# sensor.net
KiCad netlist of a schematic drawn in EAGLE
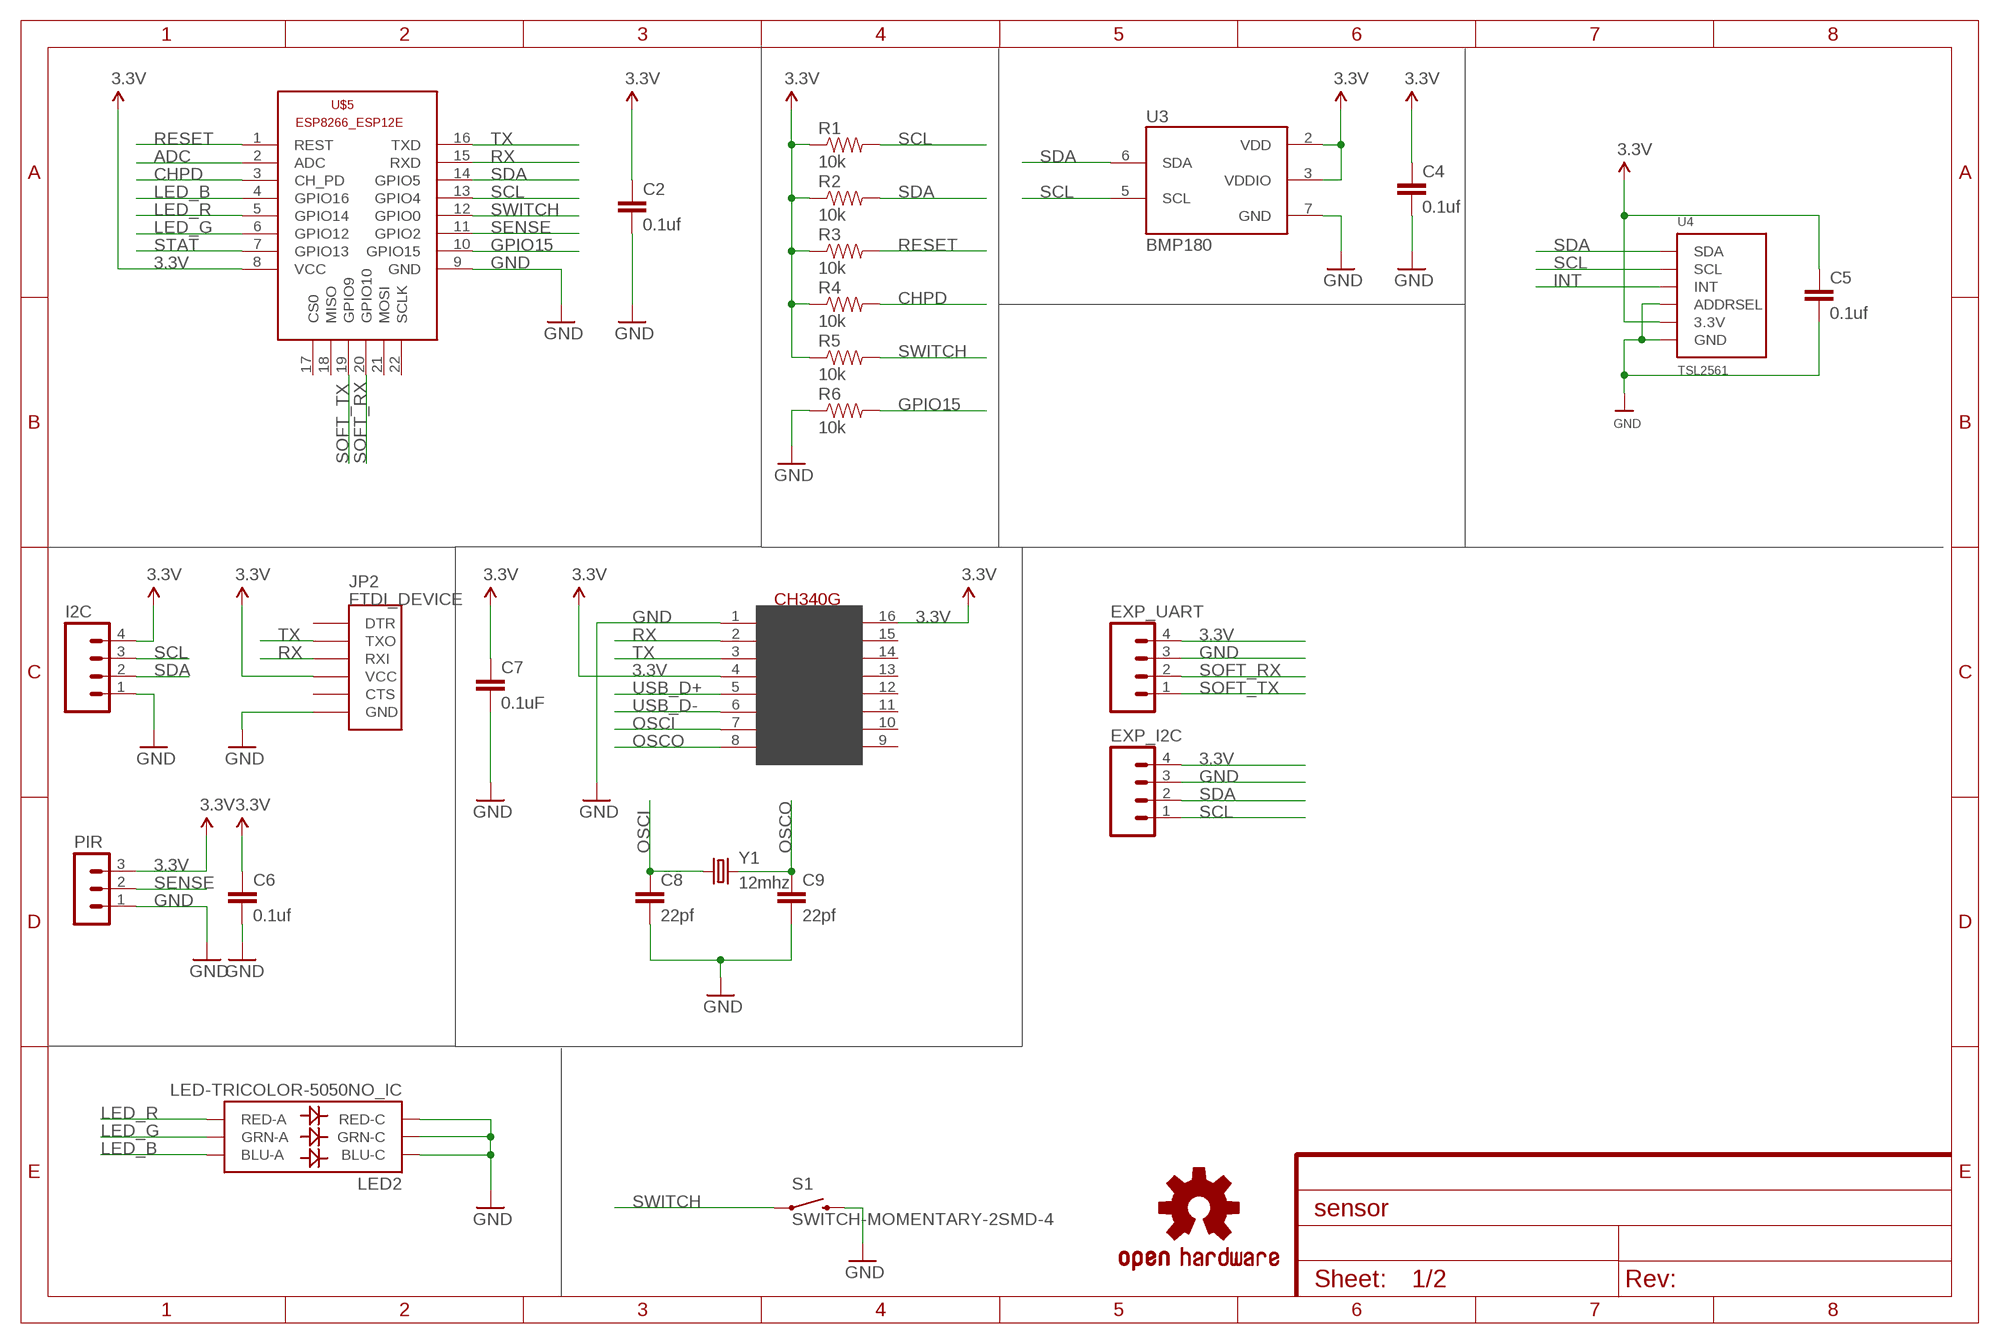
[diagram p0: schematic, sheet 1]
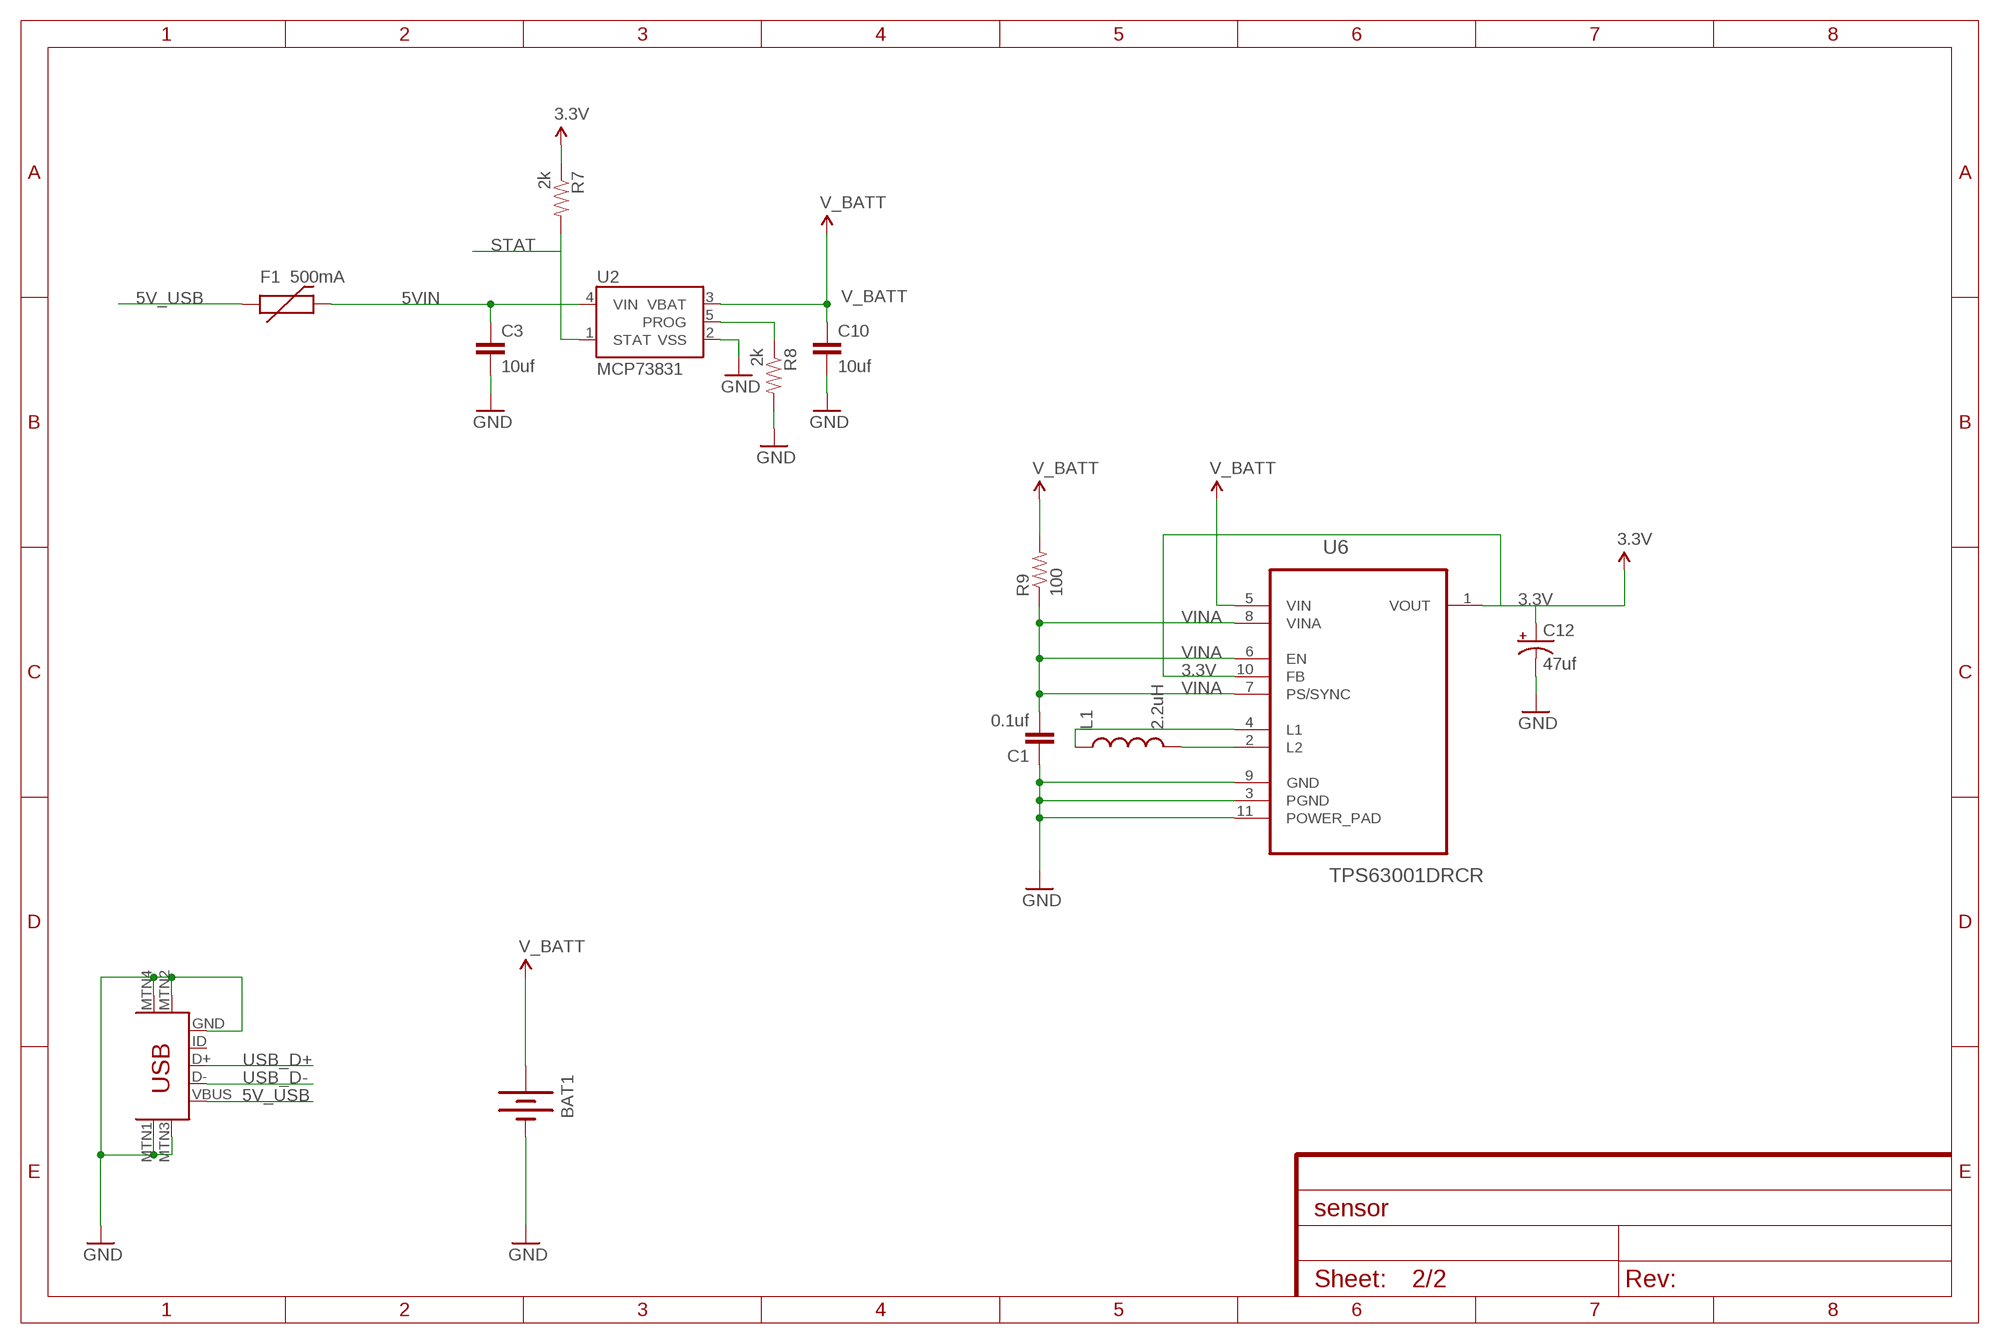
[diagram p1: schematic, sheet 2]

(export (version "E")
  (design (tool "Eeschema 10.0.6"))
  (components
    (comp (ref "BAT1")
      (value "BATTERY18650")
      (footprint "eagle-import:BATTERY_18650-HOLDER")
      (libsource (lib "eagle-import") (part "BATTERY18650"))
    )
    (comp (ref "C1")
      (value "0.1uf")
      (footprint "eagle-import:0805")
      (libsource (lib "eagle-import") (part "CAP0805"))
    )
    (comp (ref "C3")
      (value "10uf")
      (footprint "eagle-import:0805")
      (libsource (lib "eagle-import") (part "CAP0805"))
    )
    (comp (ref "C10")
      (value "10uf")
      (footprint "eagle-import:0805")
      (libsource (lib "eagle-import") (part "CAP0805"))
    )
    (comp (ref "C12")
      (value "47uf")
      (footprint "eagle-import:PANASONIC_C")
      (libsource (lib "eagle-import") (part "CAP_POLC"))
    )
    (comp (ref "F1")
      (value "500mA")
      (footprint "eagle-import:PTC-1206")
      (libsource (lib "eagle-import") (part "PTCSMD"))
    )
    (comp (ref "L1")
      (value "2.2uH")
      (footprint "eagle-import:SRU5028")
      (libsource (lib "eagle-import") (part "INDUCTORSRU5028"))
    )
    (comp (ref "R7")
      (value "2k")
      (footprint "eagle-import:0805")
      (libsource (lib "eagle-import") (part "RESISTOR0805-RES"))
    )
    (comp (ref "R8")
      (value "2k")
      (footprint "eagle-import:0805")
      (libsource (lib "eagle-import") (part "RESISTOR0805-RES"))
    )
    (comp (ref "R9")
      (value "100")
      (footprint "eagle-import:0805")
      (libsource (lib "eagle-import") (part "RESISTOR0805-RES"))
    )
    (comp (ref "U$6")
      (value "USB-MINIB-5PIN")
      (footprint "eagle-import:USB-MINIB")
      (libsource (lib "eagle-import") (part "USB-MINIB-5PIN"))
    )
    (comp (ref "U2")
      (value "MCP73831")
      (footprint "eagle-import:SOT23-5")
      (libsource (lib "eagle-import") (part "MCP73831"))
    )
    (comp (ref "U6")
      (value "TPS63001DRCR")
      (footprint "eagle-import:SON50P300X300X100-11N")
      (libsource (lib "eagle-import") (part "TPS63001DRCR"))
    )
    (comp (ref "C2")
      (value "0.1uf")
      (footprint "eagle-import:0805")
      (libsource (lib "eagle-import") (part "CAP0805"))
    )
    (comp (ref "C4")
      (value "0.1uf")
      (footprint "eagle-import:0805")
      (libsource (lib "eagle-import") (part "CAP0805"))
    )
    (comp (ref "C5")
      (value "0.1uf")
      (footprint "eagle-import:0805")
      (libsource (lib "eagle-import") (part "CAP0805"))
    )
    (comp (ref "C6")
      (value "0.1uf")
      (footprint "eagle-import:0805")
      (libsource (lib "eagle-import") (part "CAP0805"))
    )
    (comp (ref "C7")
      (value "0.1uF")
      (footprint "eagle-import:C0805")
      (libsource (lib "eagle-import") (part "C-EUC0805"))
    )
    (comp (ref "C8")
      (value "22pf")
      (footprint "eagle-import:C0805")
      (libsource (lib "eagle-import") (part "C-EUC0805"))
    )
    (comp (ref "C9")
      (value "22pf")
      (footprint "eagle-import:C0805")
      (libsource (lib "eagle-import") (part "C-EUC0805"))
    )
    (comp (ref "EXP_I2C")
      (value "M04LOCK")
      (footprint "eagle-import:1X04_LOCK")
      (libsource (lib "eagle-import") (part "M04LOCK"))
    )
    (comp (ref "EXP_UART")
      (value "M04LOCK")
      (footprint "eagle-import:1X04_LOCK")
      (libsource (lib "eagle-import") (part "M04LOCK"))
    )
    (comp (ref "I2C")
      (value "M04JST-PTH")
      (footprint "eagle-import:JST-4-PTH")
      (libsource (lib "eagle-import") (part "M04JST-PTH"))
    )
    (comp (ref "JP2")
      (value "FTDI_DEVICE")
      (footprint "eagle-import:FTDI_DEVICE_SIDE")
      (libsource (lib "eagle-import") (part "FTDI_DEVICE"))
    )
    (comp (ref "LED2")
      (value "LED-TRICOLOR-5050NO_IC")
      (footprint "eagle-import:LED-TRICOLOR-5050")
      (libsource (lib "eagle-import") (part "LED-TRICOLOR-5050NO_IC"))
    )
    (comp (ref "LOGO1")
      (value "OSHW-LOGOL")
      (footprint "eagle-import:OSHW-LOGO-L")
      (libsource (lib "eagle-import") (part "OSHW-LOGOL"))
    )
    (comp (ref "PIR")
      (value "MA03-1")
      (footprint "eagle-import:MA03-1")
      (libsource (lib "eagle-import") (part "MA03-1"))
    )
    (comp (ref "R1")
      (value "10k")
      (footprint "eagle-import:0805")
      (libsource (lib "eagle-import") (part "RESISTOR0805-RES"))
    )
    (comp (ref "R2")
      (value "10k")
      (footprint "eagle-import:0805")
      (libsource (lib "eagle-import") (part "RESISTOR0805-RES"))
    )
    (comp (ref "R3")
      (value "10k")
      (footprint "eagle-import:0805")
      (libsource (lib "eagle-import") (part "RESISTOR0805-RES"))
    )
    (comp (ref "R4")
      (value "10k")
      (footprint "eagle-import:0805")
      (libsource (lib "eagle-import") (part "RESISTOR0805-RES"))
    )
    (comp (ref "R5")
      (value "10k")
      (footprint "eagle-import:0805")
      (libsource (lib "eagle-import") (part "RESISTOR0805-RES"))
    )
    (comp (ref "R6")
      (value "10k")
      (footprint "eagle-import:0805")
      (libsource (lib "eagle-import") (part "RESISTOR0805-RES"))
    )
    (comp (ref "S1")
      (value "SWITCH-MOMENTARY-2SMD-4")
      (footprint "eagle-import:TACTILE_SWITCH_TALL")
      (libsource (lib "eagle-import") (part "SWITCH-MOMENTARY-2SMD-4"))
    )
    (comp (ref "U$5")
      (value "ESP8266-12EESP8266-ESP12E")
      (footprint "eagle-import:ESP8266-ESP12E")
      (libsource (lib "eagle-import") (part "ESP8266-12EESP8266-ESP12E"))
    )
    (comp (ref "U$11")
      (value "CH340G")
      (footprint "eagle-import:SOIC16")
      (libsource (lib "eagle-import") (part "CH340G"))
    )
    (comp (ref "U3")
      (value "BMP180")
      (footprint "eagle-import:BMP180")
      (libsource (lib "eagle-import") (part "BMP180"))
    )
    (comp (ref "U4")
      (value "TSL2561")
      (footprint "eagle-import:TSL2561_FN")
      (libsource (lib "eagle-import") (part "TSL2561"))
    )
    (comp (ref "Y1")
      (value "12mhz")
      (footprint "eagle-import:HC49UP")
      (libsource (lib "eagle-import") (part "CRYSTALSMD"))
    )
  )
  (nets
    (net (code "1") (name "3.3V") (class "Default")
      (node (ref "C12") (pin "+") (pinfunction "+_+") (pintype "passive"))
      (node (ref "C2") (pin "1") (pinfunction "1_1") (pintype "passive"))
      (node (ref "C4") (pin "1") (pinfunction "1_1") (pintype "passive"))
      (node (ref "C5") (pin "1") (pinfunction "1_1") (pintype "passive"))
      (node (ref "C6") (pin "1") (pinfunction "1_1") (pintype "passive"))
      (node (ref "C7") (pin "1") (pinfunction "1_1") (pintype "passive"))
      (node (ref "EXP_I2C") (pin "4") (pinfunction "4_4") (pintype "passive"))
      (node (ref "EXP_UART") (pin "4") (pinfunction "4_4") (pintype "passive"))
      (node (ref "I2C") (pin "4") (pinfunction "4_4") (pintype "passive"))
      (node (ref "JP2") (pin "P$4") (pinfunction "VCC_P$4") (pintype "bidirectional"))
      (node (ref "PIR") (pin "3") (pinfunction "3_3") (pintype "passive"))
      (node (ref "R1") (pin "1") (pinfunction "1_1") (pintype "passive"))
      (node (ref "R2") (pin "1") (pinfunction "1_1") (pintype "passive"))
      (node (ref "R3") (pin "1") (pinfunction "1_1") (pintype "passive"))
      (node (ref "R4") (pin "1") (pinfunction "1_1") (pintype "passive"))
      (node (ref "R5") (pin "1") (pinfunction "1_1") (pintype "passive"))
      (node (ref "R7") (pin "1") (pinfunction "1_1") (pintype "passive"))
      (node (ref "U$11") (pin "16") (pinfunction "VCC_16") (pintype "bidirectional"))
      (node (ref "U$11") (pin "4") (pinfunction "V3_4") (pintype "bidirectional"))
      (node (ref "U$5") (pin "8") (pinfunction "VCC_8") (pintype "bidirectional"))
      (node (ref "U3") (pin "2") (pinfunction "VDD_2") (pintype "power_in"))
      (node (ref "U3") (pin "3") (pinfunction "VDDIO_3") (pintype "power_in"))
      (node (ref "U4") (pin "VDD") (pinfunction "3.3V_VDD") (pintype "bidirectional"))
      (node (ref "U6") (pin "1") (pinfunction "VOUT_1") (pintype "output"))
      (node (ref "U6") (pin "10") (pinfunction "FB_10") (pintype "input"))
    )
    (net (code "2") (name "5VIN") (class "Default")
      (node (ref "C3") (pin "1") (pinfunction "1_1") (pintype "passive"))
      (node (ref "F1") (pin "2") (pinfunction "2_2") (pintype "bidirectional"))
      (node (ref "U2") (pin "4") (pinfunction "VIN_4") (pintype "power_in"))
    )
    (net (code "3") (name "5V_USB") (class "Default")
      (node (ref "F1") (pin "1") (pinfunction "1_1") (pintype "bidirectional"))
      (node (ref "U$6") (pin "VBUS") (pinfunction "VBUS_VBUS") (pintype "bidirectional"))
    )
    (net (code "4") (name "ADC") (class "Default")
      (node (ref "U$5") (pin "2") (pinfunction "ADC_2") (pintype "bidirectional"))
    )
    (net (code "5") (name "CHPD") (class "Default")
      (node (ref "R4") (pin "2") (pinfunction "2_2") (pintype "passive"))
      (node (ref "U$5") (pin "3") (pinfunction "CH_PD_3") (pintype "bidirectional"))
    )
    (net (code "6") (name "GND") (class "Default")
      (node (ref "BAT1") (pin "GND@1") (pinfunction "-_GND@1") (pintype "power_in"))
      (node (ref "C1") (pin "1") (pinfunction "1_1") (pintype "passive"))
      (node (ref "C10") (pin "2") (pinfunction "2_2") (pintype "passive"))
      (node (ref "C12") (pin "-") (pinfunction "-_-") (pintype "passive"))
      (node (ref "C2") (pin "2") (pinfunction "2_2") (pintype "passive"))
      (node (ref "C3") (pin "2") (pinfunction "2_2") (pintype "passive"))
      (node (ref "C4") (pin "2") (pinfunction "2_2") (pintype "passive"))
      (node (ref "C5") (pin "2") (pinfunction "2_2") (pintype "passive"))
      (node (ref "C6") (pin "2") (pinfunction "2_2") (pintype "passive"))
      (node (ref "C7") (pin "2") (pinfunction "2_2") (pintype "passive"))
      (node (ref "C8") (pin "2") (pinfunction "2_2") (pintype "passive"))
      (node (ref "C9") (pin "2") (pinfunction "2_2") (pintype "passive"))
      (node (ref "EXP_I2C") (pin "3") (pinfunction "3_3") (pintype "passive"))
      (node (ref "EXP_UART") (pin "3") (pinfunction "3_3") (pintype "passive"))
      (node (ref "I2C") (pin "1") (pinfunction "1_1") (pintype "passive"))
      (node (ref "JP2") (pin "P$6") (pinfunction "GND_P$6") (pintype "bidirectional"))
      (node (ref "LED2") (pin "4") (pinfunction "BLU-C_4") (pintype "bidirectional"))
      (node (ref "LED2") (pin "5") (pinfunction "RED-C_5") (pintype "bidirectional"))
      (node (ref "LED2") (pin "6") (pinfunction "GRN-C_6") (pintype "bidirectional"))
      (node (ref "PIR") (pin "1") (pinfunction "1_1") (pintype "passive"))
      (node (ref "R6") (pin "1") (pinfunction "1_1") (pintype "passive"))
      (node (ref "R8") (pin "2") (pinfunction "2_2") (pintype "passive"))
      (node (ref "S1") (pin "B2") (pinfunction "2_B2") (pintype "passive"))
      (node (ref "U$11") (pin "1") (pinfunction "GND_1") (pintype "bidirectional"))
      (node (ref "U$5") (pin "9") (pinfunction "GND_9") (pintype "bidirectional"))
      (node (ref "U$6") (pin "GND") (pinfunction "GND_GND") (pintype "bidirectional"))
      (node (ref "U$6") (pin "MTN1") (pinfunction "MTN2_MTN1") (pintype "bidirectional"))
      (node (ref "U$6") (pin "MTN2") (pinfunction "MTN3_MTN2") (pintype "bidirectional"))
      (node (ref "U$6") (pin "MTN3") (pinfunction "MTN1_MTN3") (pintype "bidirectional"))
      (node (ref "U$6") (pin "MTN4") (pinfunction "MTN4_MTN4") (pintype "bidirectional"))
      (node (ref "U2") (pin "2") (pinfunction "VSS_2") (pintype "power_in"))
      (node (ref "U3") (pin "7") (pinfunction "GND_7") (pintype "power_in"))
      (node (ref "U4") (pin "ADR") (pinfunction "ADDRSEL_ADR") (pintype "bidirectional"))
      (node (ref "U4") (pin "VSS") (pinfunction "GND_VSS") (pintype "bidirectional"))
      (node (ref "U6") (pin "11") (pinfunction "POWER_PAD_11") (pintype "passive"))
      (node (ref "U6") (pin "3") (pinfunction "PGND_3") (pintype "passive"))
      (node (ref "U6") (pin "9") (pinfunction "GND_9") (pintype "passive"))
    )
    (net (code "7") (name "GPIO15") (class "Default")
      (node (ref "R6") (pin "2") (pinfunction "2_2") (pintype "passive"))
      (node (ref "U$5") (pin "10") (pinfunction "GPIO15_10") (pintype "bidirectional"))
    )
    (net (code "8") (name "INT") (class "Default")
      (node (ref "U4") (pin "INT") (pinfunction "INT_INT") (pintype "bidirectional"))
    )
    (net (code "9") (name "LED_B") (class "Default")
      (node (ref "LED2") (pin "3") (pinfunction "BLU-A_3") (pintype "bidirectional"))
      (node (ref "U$5") (pin "4") (pinfunction "GPIO16_4") (pintype "bidirectional"))
    )
    (net (code "10") (name "LED_G") (class "Default")
      (node (ref "LED2") (pin "1") (pinfunction "GRN-A_1") (pintype "bidirectional"))
      (node (ref "U$5") (pin "6") (pinfunction "GPIO12_6") (pintype "bidirectional"))
    )
    (net (code "11") (name "LED_R") (class "Default")
      (node (ref "LED2") (pin "2") (pinfunction "RED-A_2") (pintype "bidirectional"))
      (node (ref "U$5") (pin "5") (pinfunction "GPIO14_5") (pintype "bidirectional"))
    )
    (net (code "12") (name "Net-(U2-PROG)") (class "Default")
      (node (ref "R8") (pin "1") (pinfunction "1_1") (pintype "passive"))
      (node (ref "U2") (pin "5") (pinfunction "PROG_5") (pintype "input"))
    )
    (net (code "13") (name "Net-(U6-L1)") (class "Default")
      (node (ref "L1") (pin "1") (pinfunction "1_1") (pintype "passive"))
      (node (ref "U6") (pin "4") (pinfunction "L1_4") (pintype "passive"))
    )
    (net (code "14") (name "Net-(U6-L2)") (class "Default")
      (node (ref "L1") (pin "2") (pinfunction "2_2") (pintype "passive"))
      (node (ref "U6") (pin "2") (pinfunction "L2_2") (pintype "passive"))
    )
    (net (code "15") (name "OSCI") (class "Default")
      (node (ref "C8") (pin "1") (pinfunction "1_1") (pintype "passive"))
      (node (ref "U$11") (pin "7") (pinfunction "XI_7") (pintype "bidirectional"))
      (node (ref "Y1") (pin "1") (pinfunction "1_1") (pintype "passive"))
    )
    (net (code "16") (name "OSCO") (class "Default")
      (node (ref "C9") (pin "1") (pinfunction "1_1") (pintype "passive"))
      (node (ref "U$11") (pin "8") (pinfunction "XO_8") (pintype "bidirectional"))
      (node (ref "Y1") (pin "2") (pinfunction "2_2") (pintype "passive"))
    )
    (net (code "17") (name "RESET") (class "Default")
      (node (ref "R3") (pin "2") (pinfunction "2_2") (pintype "passive"))
      (node (ref "U$5") (pin "1") (pinfunction "REST_1") (pintype "bidirectional"))
    )
    (net (code "18") (name "RX") (class "Default")
      (node (ref "JP2") (pin "P$3") (pinfunction "RXI_P$3") (pintype "bidirectional"))
      (node (ref "U$11") (pin "2") (pinfunction "TX_2") (pintype "bidirectional"))
      (node (ref "U$5") (pin "15") (pinfunction "RXD_15") (pintype "bidirectional"))
    )
    (net (code "19") (name "SCL") (class "Default")
      (node (ref "EXP_I2C") (pin "1") (pinfunction "1_1") (pintype "passive"))
      (node (ref "I2C") (pin "3") (pinfunction "3_3") (pintype "passive"))
      (node (ref "R1") (pin "2") (pinfunction "2_2") (pintype "passive"))
      (node (ref "U$5") (pin "13") (pinfunction "GPIO4_13") (pintype "bidirectional"))
      (node (ref "U3") (pin "5") (pinfunction "SCL_5") (pintype "input"))
      (node (ref "U4") (pin "CLK") (pinfunction "SCL_CLK") (pintype "bidirectional"))
    )
    (net (code "20") (name "SDA") (class "Default")
      (node (ref "EXP_I2C") (pin "2") (pinfunction "2_2") (pintype "passive"))
      (node (ref "I2C") (pin "2") (pinfunction "2_2") (pintype "passive"))
      (node (ref "R2") (pin "2") (pinfunction "2_2") (pintype "passive"))
      (node (ref "U$5") (pin "14") (pinfunction "GPIO5_14") (pintype "bidirectional"))
      (node (ref "U3") (pin "6") (pinfunction "SDA_6") (pintype "bidirectional"))
      (node (ref "U4") (pin "DATA") (pinfunction "SDA_DATA") (pintype "bidirectional"))
    )
    (net (code "21") (name "SENSE") (class "Default")
      (node (ref "PIR") (pin "2") (pinfunction "2_2") (pintype "passive"))
      (node (ref "U$5") (pin "11") (pinfunction "GPIO2_11") (pintype "bidirectional"))
    )
    (net (code "22") (name "SOFT_RX") (class "Default")
      (node (ref "EXP_UART") (pin "2") (pinfunction "2_2") (pintype "passive"))
      (node (ref "U$5") (pin "20") (pinfunction "GPIO10_20") (pintype "bidirectional"))
    )
    (net (code "23") (name "SOFT_TX") (class "Default")
      (node (ref "EXP_UART") (pin "1") (pinfunction "1_1") (pintype "passive"))
      (node (ref "U$5") (pin "19") (pinfunction "GPIO9_19") (pintype "bidirectional"))
    )
    (net (code "24") (name "STAT") (class "Default")
      (node (ref "R7") (pin "2") (pinfunction "2_2") (pintype "passive"))
      (node (ref "U$5") (pin "7") (pinfunction "GPIO13_7") (pintype "bidirectional"))
      (node (ref "U2") (pin "1") (pinfunction "STAT_1") (pintype "output"))
    )
    (net (code "25") (name "SWITCH") (class "Default")
      (node (ref "R5") (pin "2") (pinfunction "2_2") (pintype "passive"))
      (node (ref "S1") (pin "A2") (pinfunction "1_A2") (pintype "passive"))
      (node (ref "U$5") (pin "12") (pinfunction "GPIO0_12") (pintype "bidirectional"))
    )
    (net (code "26") (name "TX") (class "Default")
      (node (ref "JP2") (pin "P$2") (pinfunction "TXO_P$2") (pintype "bidirectional"))
      (node (ref "U$11") (pin "3") (pinfunction "RX_3") (pintype "bidirectional"))
      (node (ref "U$5") (pin "16") (pinfunction "TXD_16") (pintype "bidirectional"))
    )
    (net (code "27") (name "USB_D+") (class "Default")
      (node (ref "U$11") (pin "5") (pinfunction "D+_5") (pintype "bidirectional"))
      (node (ref "U$6") (pin "D+") (pinfunction "D+_D+") (pintype "bidirectional"))
    )
    (net (code "28") (name "USB_D-") (class "Default")
      (node (ref "U$11") (pin "6") (pinfunction "D-_6") (pintype "bidirectional"))
      (node (ref "U$6") (pin "D-") (pinfunction "D-_D-") (pintype "bidirectional"))
    )
    (net (code "29") (name "VINA") (class "Default")
      (node (ref "C1") (pin "2") (pinfunction "2_2") (pintype "passive"))
      (node (ref "R9") (pin "1") (pinfunction "1_1") (pintype "passive"))
      (node (ref "U6") (pin "6") (pinfunction "EN_6") (pintype "input"))
      (node (ref "U6") (pin "7") (pinfunction "PS/SYNC_7") (pintype "input"))
      (node (ref "U6") (pin "8") (pinfunction "VINA_8") (pintype "power_in"))
    )
    (net (code "30") (name "V_BATT") (class "Default")
      (node (ref "BAT1") (pin "PWR@1") (pinfunction "+_PWR@1") (pintype "power_in"))
      (node (ref "C10") (pin "1") (pinfunction "1_1") (pintype "passive"))
      (node (ref "R9") (pin "2") (pinfunction "2_2") (pintype "passive"))
      (node (ref "U2") (pin "3") (pinfunction "VBAT_3") (pintype "power_in"))
      (node (ref "U6") (pin "5") (pinfunction "VIN_5") (pintype "power_in"))
    )
    (net (code "31") (name "unconnected-(JP2-CTS-PadP$5)") (class "Default")
      (node (ref "JP2") (pin "P$5") (pinfunction "CTS_P$5") (pintype "bidirectional"))
    )
    (net (code "32") (name "unconnected-(JP2-DTR-PadP$1)") (class "Default")
      (node (ref "JP2") (pin "P$1") (pinfunction "DTR_P$1") (pintype "bidirectional"))
    )
    (net (code "33") (name "unconnected-(U$5-CS0-Pad17)") (class "Default")
      (node (ref "U$5") (pin "17") (pinfunction "CS0_17") (pintype "bidirectional"))
    )
    (net (code "34") (name "unconnected-(U$5-MISO-Pad18)") (class "Default")
      (node (ref "U$5") (pin "18") (pinfunction "MISO_18") (pintype "bidirectional"))
    )
    (net (code "35") (name "unconnected-(U$5-MOSI-Pad21)") (class "Default")
      (node (ref "U$5") (pin "21") (pinfunction "MOSI_21") (pintype "bidirectional"))
    )
    (net (code "36") (name "unconnected-(U$5-SCLK-Pad22)") (class "Default")
      (node (ref "U$5") (pin "22") (pinfunction "SCLK_22") (pintype "bidirectional"))
    )
    (net (code "37") (name "unconnected-(U$6-PadID)") (class "Default")
      (node (ref "U$6") (pin "ID") (pinfunction "ID_ID") (pintype "bidirectional"))
    )
    (net (code "38") (name "unconnected-(U$11-CTS-Pad9)") (class "Default")
      (node (ref "U$11") (pin "9") (pinfunction "CTS_9") (pintype "bidirectional"))
    )
    (net (code "39") (name "unconnected-(U$11-DCD-Pad12)") (class "Default")
      (node (ref "U$11") (pin "12") (pinfunction "DCD_12") (pintype "bidirectional"))
    )
    (net (code "40") (name "unconnected-(U$11-DSR-Pad10)") (class "Default")
      (node (ref "U$11") (pin "10") (pinfunction "DSR_10") (pintype "bidirectional"))
    )
    (net (code "41") (name "unconnected-(U$11-DTR-Pad13)") (class "Default")
      (node (ref "U$11") (pin "13") (pinfunction "DTR_13") (pintype "bidirectional"))
    )
    (net (code "42") (name "unconnected-(U$11-RI-Pad11)") (class "Default")
      (node (ref "U$11") (pin "11") (pinfunction "RI_11") (pintype "bidirectional"))
    )
    (net (code "43") (name "unconnected-(U$11-RS232-Pad15)") (class "Default")
      (node (ref "U$11") (pin "15") (pinfunction "RS232_15") (pintype "bidirectional"))
    )
    (net (code "44") (name "unconnected-(U$11-RTS-Pad14)") (class "Default")
      (node (ref "U$11") (pin "14") (pinfunction "RTS_14") (pintype "bidirectional"))
    )
  )
)
